# light-box-controller.net
KiCad netlist of a schematic drawn in EAGLE
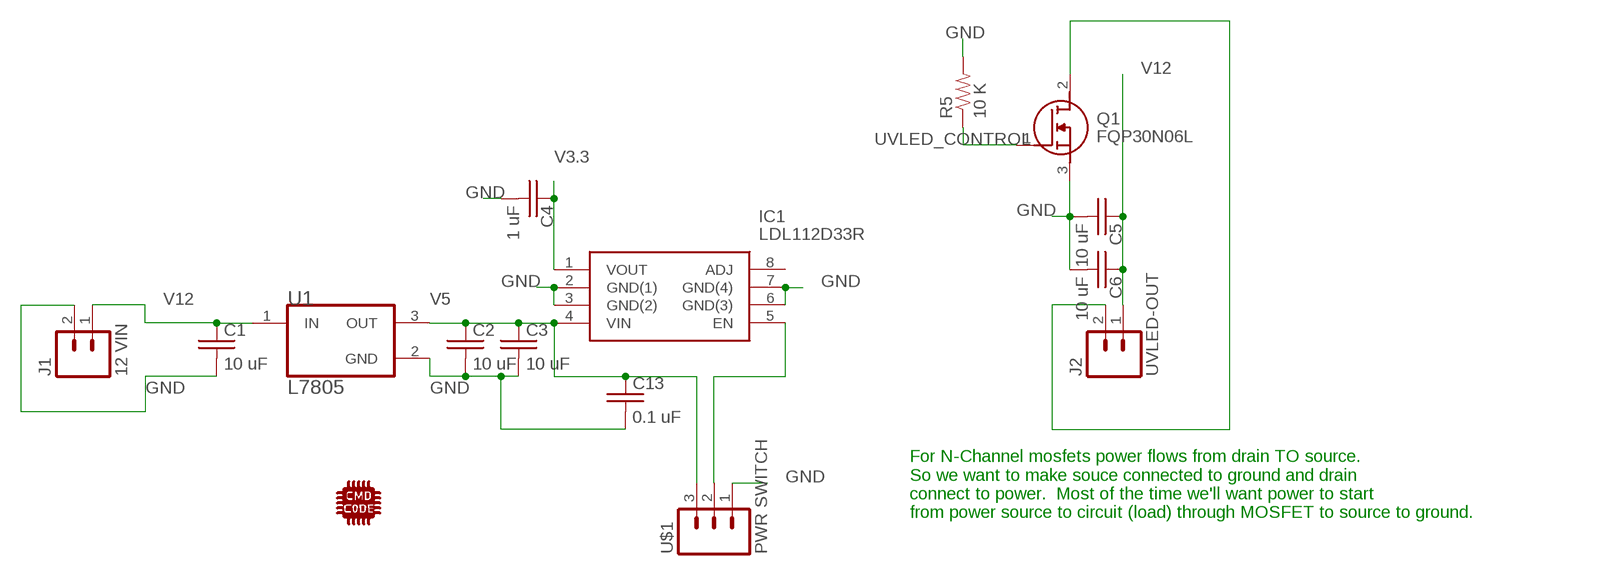
[diagram p0: schematic, sheet 1]
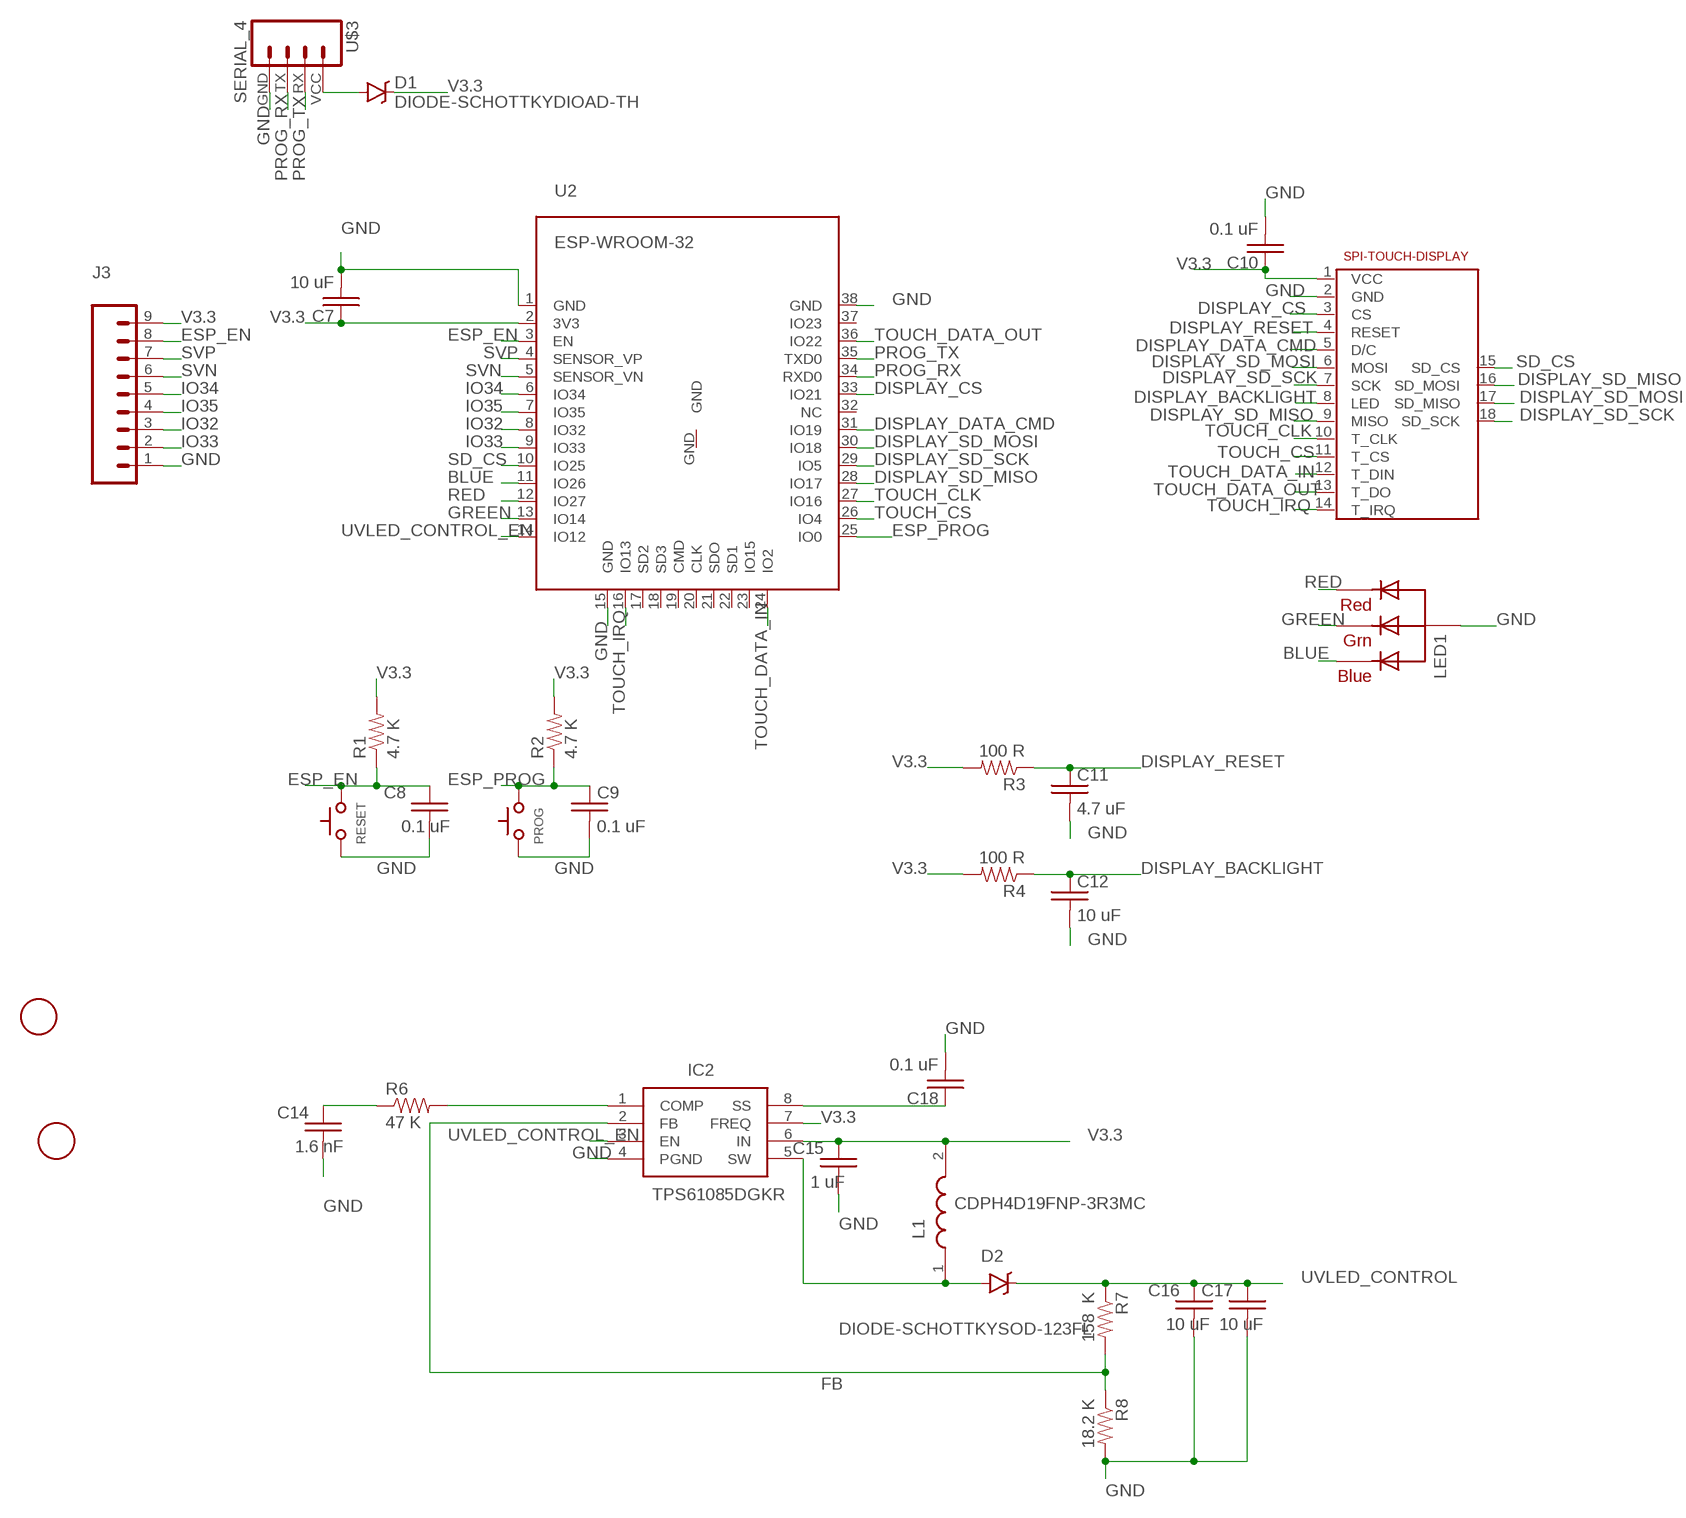
[diagram p1: schematic, sheet 2]

(export (version "E")
  (design (tool "Eeschema 10.0.6"))
  (components
    (comp (ref "C1")
      (value "10 uF")
      (footprint "eagle-import:C0805K")
      (libsource (lib "eagle-import") (part "C-USC0805K"))
    )
    (comp (ref "C2")
      (value "10 uF")
      (footprint "eagle-import:C0805K")
      (libsource (lib "eagle-import") (part "C-USC0805K"))
    )
    (comp (ref "C3")
      (value "10 uF")
      (footprint "eagle-import:C0805K")
      (libsource (lib "eagle-import") (part "C-USC0805K"))
    )
    (comp (ref "C4")
      (value "1 uF")
      (footprint "eagle-import:C0805K")
      (libsource (lib "eagle-import") (part "C-USC0805K"))
    )
    (comp (ref "C5")
      (value "10 uF")
      (footprint "eagle-import:C0805K")
      (libsource (lib "eagle-import") (part "C-USC0805K"))
    )
    (comp (ref "C6")
      (value "10 uF")
      (footprint "eagle-import:C0805K")
      (libsource (lib "eagle-import") (part "C-USC0805K"))
    )
    (comp (ref "C13")
      (value "0.1 uF")
      (footprint "eagle-import:C0805K")
      (libsource (lib "eagle-import") (part "C-USC0805K"))
    )
    (comp (ref "IC1")
      (value "LDL112D33R")
      (footprint "eagle-import:SOIC127P600X175-8N")
      (libsource (lib "eagle-import") (part "LDL112D33R"))
    )
    (comp (ref "J1")
      (value "12 VIN")
      (footprint "eagle-import:SCREWTERMINAL-5MM-2")
      (libsource (lib "eagle-import") (part "M025MM"))
    )
    (comp (ref "J2")
      (value "UVLED-OUT")
      (footprint "eagle-import:SCREWTERMINAL-5MM-2")
      (libsource (lib "eagle-import") (part "M025MM"))
    )
    (comp (ref "Q1")
      (value "FQP30N06L")
      (footprint "eagle-import:TO254P470X1016X2019-3P")
      (fields (field (name "MOUSER_PART_NUMBER") "512-FQP30N06L") (field (name "RS_PART_NUMBER") "8075863P"))
      (libsource (lib "eagle-import") (part "FQP30N06L"))
    )
    (comp (ref "R5")
      (value "10 K")
      (footprint "eagle-import:0805")
      (libsource (lib "eagle-import") (part "RESISTOR0805-RES"))
    )
    (comp (ref "U$1")
      (value "PWR SWITCH")
      (footprint "eagle-import:1X03_LONGPADS")
      (libsource (lib "eagle-import") (part "M03LONGPADS"))
    )
    (comp (ref "U$4")
      (value "CMD_C0DE_LOGOCMD_CODE_LOGO_SILK")
      (footprint "eagle-import:CMD_C0DE_LOGO_SILK")
      (libsource (lib "eagle-import") (part "CMD_C0DE_LOGOCMD_CODE_LOGO_SILK"))
    )
    (comp (ref "U1")
      (value "L7805")
      (footprint "eagle-import:TO-220-3")
      (fields (field (name "MF") "STMicroelectronics"))
      (libsource (lib "eagle-import") (part "L7805"))
    )
    (comp (ref "C7")
      (value "10 uF")
      (footprint "eagle-import:C0805K")
      (libsource (lib "eagle-import") (part "C-USC0805K"))
    )
    (comp (ref "C8")
      (value "0.1 uF")
      (footprint "eagle-import:C0805K")
      (libsource (lib "eagle-import") (part "C-USC0805K"))
    )
    (comp (ref "C9")
      (value "0.1 uF")
      (footprint "eagle-import:C0805K")
      (libsource (lib "eagle-import") (part "C-USC0805K"))
    )
    (comp (ref "C10")
      (value "0.1 uF")
      (footprint "eagle-import:C0805K")
      (libsource (lib "eagle-import") (part "C-USC0805K"))
    )
    (comp (ref "C11")
      (value "4.7 uF")
      (footprint "eagle-import:C0805K")
      (libsource (lib "eagle-import") (part "C-USC0805K"))
    )
    (comp (ref "C12")
      (value "10 uF")
      (footprint "eagle-import:C0805K")
      (libsource (lib "eagle-import") (part "C-USC0805K"))
    )
    (comp (ref "C14")
      (value "1.6 nF")
      (footprint "eagle-import:C0805K")
      (libsource (lib "eagle-import") (part "C-USC0805K"))
    )
    (comp (ref "C15")
      (value "1 uF")
      (footprint "eagle-import:C0805K")
      (libsource (lib "eagle-import") (part "C-USC0805K"))
    )
    (comp (ref "C16")
      (value "10 uF")
      (footprint "eagle-import:C0805K")
      (libsource (lib "eagle-import") (part "C-USC0805K"))
    )
    (comp (ref "C17")
      (value "10 uF")
      (footprint "eagle-import:C0805K")
      (libsource (lib "eagle-import") (part "C-USC0805K"))
    )
    (comp (ref "C18")
      (value "0.1 uF")
      (footprint "eagle-import:C0805K")
      (libsource (lib "eagle-import") (part "C-USC0805K"))
    )
    (comp (ref "D1")
      (value "DIODE-SCHOTTKYDIOAD-TH")
      (footprint "eagle-import:DIOAD1060W80L520D270")
      (libsource (lib "eagle-import") (part "DIODE-SCHOTTKYDIOAD-TH"))
    )
    (comp (ref "D2")
      (value "DIODE-SCHOTTKYSOD-123FL")
      (footprint "eagle-import:SOD-123FL")
      (libsource (lib "eagle-import") (part "DIODE-SCHOTTKYSOD-123FL"))
    )
    (comp (ref "IC2")
      (value "TPS61085DGKR")
      (footprint "eagle-import:SOP65P490X110-8N")
      (fields (field (name "MOUSER_PART_NUMBER") "595-TPS61085DGKR"))
      (libsource (lib "eagle-import") (part "TPS61085DGKR"))
    )
    (comp (ref "J3")
      (value "M09LONGPADS")
      (footprint "eagle-import:1X09_LONGPADS")
      (libsource (lib "eagle-import") (part "M09LONGPADS"))
    )
    (comp (ref "L1")
      (value "CDPH4D19FNP-3R3MC")
      (footprint "eagle-import:CDPH4D19FNP3R3MC")
      (fields (field (name "MOUSER_PART_NUMBER") "851-CDPH4D19FNP3R3MC"))
      (libsource (lib "eagle-import") (part "CDPH4D19FNP-3R3MC"))
    )
    (comp (ref "LED1")
      (value "RGBLED_CA-PIRANHA")
      (footprint "eagle-import:PIRANHA5MM")
      (libsource (lib "eagle-import") (part "RGBLED_CA-PIRANHA"))
    )
    (comp (ref "PROG")
      (value "SWITCH_TACTILETACTILE-2PIN-NARROW")
      (footprint "eagle-import:TACTILE-2PIN-NARROW")
      (libsource (lib "eagle-import") (part "SWITCH_TACTILETACTILE-2PIN-NARROW"))
    )
    (comp (ref "R1")
      (value "4.7 K")
      (footprint "eagle-import:0805")
      (libsource (lib "eagle-import") (part "RESISTOR0805-RES"))
    )
    (comp (ref "R2")
      (value "4.7 K")
      (footprint "eagle-import:0805")
      (libsource (lib "eagle-import") (part "RESISTOR0805-RES"))
    )
    (comp (ref "R3")
      (value "100 R")
      (footprint "eagle-import:0805")
      (libsource (lib "eagle-import") (part "RESISTOR0805-RES"))
    )
    (comp (ref "R4")
      (value "100 R")
      (footprint "eagle-import:0805")
      (libsource (lib "eagle-import") (part "RESISTOR0805-RES"))
    )
    (comp (ref "R6")
      (value "47 K")
      (footprint "eagle-import:0805")
      (libsource (lib "eagle-import") (part "RESISTOR0805-RES"))
    )
    (comp (ref "R7")
      (value "158 K")
      (footprint "eagle-import:0805")
      (libsource (lib "eagle-import") (part "RESISTOR0805-RES"))
    )
    (comp (ref "R8")
      (value "18.2 K")
      (footprint "eagle-import:0805")
      (libsource (lib "eagle-import") (part "RESISTOR0805-RES"))
    )
    (comp (ref "RESET")
      (value "SWITCH_TACTILETACTILE-2PIN-NARROW")
      (footprint "eagle-import:TACTILE-2PIN-NARROW")
      (libsource (lib "eagle-import") (part "SWITCH_TACTILETACTILE-2PIN-NARROW"))
    )
    (comp (ref "U$2")
      (value "2.4-SPI-TFT-TOUCH-SSD-MODULE")
      (footprint "eagle-import:2.4-SPI-TFT-TOUCH-SSD-MODULE")
      (libsource (lib "eagle-import") (part "2.4-SPI-TFT-TOUCH-SSD-MODULE"))
    )
    (comp (ref "U$3")
      (value "SERIAL_4")
      (footprint "eagle-import:SERIAL_HEADER_4")
      (libsource (lib "eagle-import") (part "SERIAL_4"))
    )
    (comp (ref "U$5")
      (value "FIDUCIAL")
      (footprint "eagle-import:FIDUCIAL_1MM")
      (libsource (lib "eagle-import") (part "FIDUCIAL"))
    )
    (comp (ref "U$6")
      (value "FIDUCIAL")
      (footprint "eagle-import:FIDUCIAL_1MM")
      (libsource (lib "eagle-import") (part "FIDUCIAL"))
    )
    (comp (ref "U2")
      (value "ESP-WROOM-32")
      (footprint "eagle-import:ESP-WROOM-32")
      (libsource (lib "eagle-import") (part "ESP-WROOM-32"))
    )
  )
  (nets
    (net (code "1") (name "BLUE") (class "Default")
      (node (ref "LED1") (pin "1") (pinfunction "BLUE_1") (pintype "bidirectional"))
      (node (ref "U2") (pin "11") (pinfunction "IO26_11") (pintype "bidirectional"))
    )
    (net (code "2") (name "DISPLAY_BACKLIGHT") (class "Default")
      (node (ref "C12") (pin "1") (pinfunction "1_1") (pintype "passive"))
      (node (ref "R4") (pin "1") (pinfunction "1_1") (pintype "passive"))
      (node (ref "U$2") (pin "8") (pinfunction "LED_8") (pintype "bidirectional"))
    )
    (net (code "3") (name "DISPLAY_CS") (class "Default")
      (node (ref "U$2") (pin "3") (pinfunction "CS_3") (pintype "bidirectional"))
      (node (ref "U2") (pin "33") (pinfunction "IO21_33") (pintype "bidirectional"))
    )
    (net (code "4") (name "DISPLAY_DATA_CMD") (class "Default")
      (node (ref "U$2") (pin "5") (pinfunction "D/C_5") (pintype "bidirectional"))
      (node (ref "U2") (pin "31") (pinfunction "IO19_31") (pintype "bidirectional"))
    )
    (net (code "5") (name "DISPLAY_RESET") (class "Default")
      (node (ref "C11") (pin "1") (pinfunction "1_1") (pintype "passive"))
      (node (ref "R3") (pin "1") (pinfunction "1_1") (pintype "passive"))
      (node (ref "U$2") (pin "4") (pinfunction "RESET_4") (pintype "bidirectional"))
    )
    (net (code "6") (name "DISPLAY_SD_MISO") (class "Default")
      (node (ref "U$2") (pin "16") (pinfunction "SD_MOSI_16") (pintype "bidirectional"))
      (node (ref "U$2") (pin "9") (pinfunction "MISO_9") (pintype "bidirectional"))
      (node (ref "U2") (pin "28") (pinfunction "IO17_28") (pintype "bidirectional"))
    )
    (net (code "7") (name "DISPLAY_SD_MOSI") (class "Default")
      (node (ref "U$2") (pin "17") (pinfunction "SD_MISO_17") (pintype "bidirectional"))
      (node (ref "U$2") (pin "6") (pinfunction "MOSI_6") (pintype "bidirectional"))
      (node (ref "U2") (pin "30") (pinfunction "IO18_30") (pintype "bidirectional"))
    )
    (net (code "8") (name "DISPLAY_SD_SCK") (class "Default")
      (node (ref "U$2") (pin "18") (pinfunction "SD_SCK_18") (pintype "bidirectional"))
      (node (ref "U$2") (pin "7") (pinfunction "SCK_7") (pintype "bidirectional"))
      (node (ref "U2") (pin "29") (pinfunction "IO5_29") (pintype "bidirectional"))
    )
    (net (code "9") (name "ESP_EN") (class "Default")
      (node (ref "C8") (pin "1") (pinfunction "1_1") (pintype "passive"))
      (node (ref "J3") (pin "8") (pinfunction "8_8") (pintype "passive"))
      (node (ref "R1") (pin "1") (pinfunction "1_1") (pintype "passive"))
      (node (ref "RESET") (pin "P$1") (pinfunction "A_P$1") (pintype "passive"))
      (node (ref "U2") (pin "3") (pinfunction "EN_3") (pintype "bidirectional"))
    )
    (net (code "10") (name "ESP_PROG") (class "Default")
      (node (ref "C9") (pin "1") (pinfunction "1_1") (pintype "passive"))
      (node (ref "PROG") (pin "P$1") (pinfunction "A_P$1") (pintype "passive"))
      (node (ref "R2") (pin "1") (pinfunction "1_1") (pintype "passive"))
      (node (ref "U2") (pin "25") (pinfunction "IO0_25") (pintype "bidirectional"))
    )
    (net (code "11") (name "FB") (class "Default")
      (node (ref "IC2") (pin "2") (pinfunction "FB_2") (pintype "bidirectional"))
      (node (ref "R7") (pin "2") (pinfunction "2_2") (pintype "passive"))
      (node (ref "R8") (pin "1") (pinfunction "1_1") (pintype "passive"))
    )
    (net (code "12") (name "GND") (class "Default")
      (node (ref "C1") (pin "2") (pinfunction "2_2") (pintype "passive"))
      (node (ref "C10") (pin "2") (pinfunction "2_2") (pintype "passive"))
      (node (ref "C11") (pin "2") (pinfunction "2_2") (pintype "passive"))
      (node (ref "C12") (pin "2") (pinfunction "2_2") (pintype "passive"))
      (node (ref "C13") (pin "2") (pinfunction "2_2") (pintype "passive"))
      (node (ref "C14") (pin "2") (pinfunction "2_2") (pintype "passive"))
      (node (ref "C15") (pin "2") (pinfunction "2_2") (pintype "passive"))
      (node (ref "C16") (pin "2") (pinfunction "2_2") (pintype "passive"))
      (node (ref "C17") (pin "2") (pinfunction "2_2") (pintype "passive"))
      (node (ref "C18") (pin "2") (pinfunction "2_2") (pintype "passive"))
      (node (ref "C2") (pin "2") (pinfunction "2_2") (pintype "passive"))
      (node (ref "C3") (pin "2") (pinfunction "2_2") (pintype "passive"))
      (node (ref "C4") (pin "2") (pinfunction "2_2") (pintype "passive"))
      (node (ref "C5") (pin "2") (pinfunction "2_2") (pintype "passive"))
      (node (ref "C6") (pin "2") (pinfunction "2_2") (pintype "passive"))
      (node (ref "C7") (pin "2") (pinfunction "2_2") (pintype "passive"))
      (node (ref "C8") (pin "2") (pinfunction "2_2") (pintype "passive"))
      (node (ref "C9") (pin "2") (pinfunction "2_2") (pintype "passive"))
      (node (ref "IC1") (pin "2") (pinfunction "GND(1)_2") (pintype "bidirectional"))
      (node (ref "IC1") (pin "3") (pinfunction "GND(2)_3") (pintype "bidirectional"))
      (node (ref "IC1") (pin "6") (pinfunction "GND(3)_6") (pintype "bidirectional"))
      (node (ref "IC1") (pin "7") (pinfunction "GND(4)_7") (pintype "bidirectional"))
      (node (ref "IC2") (pin "4") (pinfunction "PGND_4") (pintype "bidirectional"))
      (node (ref "J1") (pin "2") (pinfunction "2_2") (pintype "passive"))
      (node (ref "J3") (pin "1") (pinfunction "1_1") (pintype "passive"))
      (node (ref "LED1") (pin "4") (pinfunction "VCC_4") (pintype "bidirectional"))
      (node (ref "PROG") (pin "P$2") (pinfunction "C_P$2") (pintype "passive"))
      (node (ref "Q1") (pin "3") (pinfunction "S_3") (pintype "bidirectional"))
      (node (ref "R5") (pin "2") (pinfunction "2_2") (pintype "passive"))
      (node (ref "R8") (pin "2") (pinfunction "2_2") (pintype "passive"))
      (node (ref "RESET") (pin "P$2") (pinfunction "C_P$2") (pintype "passive"))
      (node (ref "U$1") (pin "1") (pinfunction "1_1") (pintype "passive"))
      (node (ref "U$2") (pin "2") (pinfunction "GND_2") (pintype "power_in"))
      (node (ref "U$3") (pin "GND") (pinfunction "GND_GND") (pintype "power_in"))
      (node (ref "U1") (pin "2") (pinfunction "GND_2") (pintype "power_in"))
      (node (ref "U2") (pin "1") (pinfunction "GND_1") (pintype "bidirectional"))
      (node (ref "U2") (pin "15") (pinfunction "GND_15") (pintype "bidirectional"))
      (node (ref "U2") (pin "38") (pinfunction "GND_38") (pintype "bidirectional"))
    )
    (net (code "13") (name "GREEN") (class "Default")
      (node (ref "LED1") (pin "3") (pinfunction "GREEN_3") (pintype "bidirectional"))
      (node (ref "U2") (pin "13") (pinfunction "IO14_13") (pintype "bidirectional"))
    )
    (net (code "14") (name "IO32") (class "Default")
      (node (ref "J3") (pin "3") (pinfunction "3_3") (pintype "passive"))
      (node (ref "U2") (pin "8") (pinfunction "IO32_8") (pintype "bidirectional"))
    )
    (net (code "15") (name "IO33") (class "Default")
      (node (ref "J3") (pin "2") (pinfunction "2_2") (pintype "passive"))
      (node (ref "U2") (pin "9") (pinfunction "IO33_9") (pintype "bidirectional"))
    )
    (net (code "16") (name "IO34") (class "Default")
      (node (ref "J3") (pin "5") (pinfunction "5_5") (pintype "passive"))
      (node (ref "U2") (pin "6") (pinfunction "IO34_6") (pintype "bidirectional"))
    )
    (net (code "17") (name "IO35") (class "Default")
      (node (ref "J3") (pin "4") (pinfunction "4_4") (pintype "passive"))
      (node (ref "U2") (pin "7") (pinfunction "IO35_7") (pintype "bidirectional"))
    )
    (net (code "18") (name "Net-(C14-Pad1)") (class "Default")
      (node (ref "C14") (pin "1") (pinfunction "1_1") (pintype "passive"))
      (node (ref "R6") (pin "1") (pinfunction "1_1") (pintype "passive"))
    )
    (net (code "19") (name "Net-(D1-PadA)") (class "Default")
      (node (ref "D1") (pin "A") (pinfunction "A_A") (pintype "passive"))
      (node (ref "U$3") (pin "VCC") (pinfunction "VCC_VCC") (pintype "power_in"))
    )
    (net (code "20") (name "Net-(IC1-EN)") (class "Default")
      (node (ref "IC1") (pin "5") (pinfunction "EN_5") (pintype "bidirectional"))
      (node (ref "U$1") (pin "2") (pinfunction "2_2") (pintype "passive"))
    )
    (net (code "21") (name "Net-(IC2-COMP)") (class "Default")
      (node (ref "IC2") (pin "1") (pinfunction "COMP_1") (pintype "bidirectional"))
      (node (ref "R6") (pin "2") (pinfunction "2_2") (pintype "passive"))
    )
    (net (code "22") (name "Net-(IC2-SS)") (class "Default")
      (node (ref "C18") (pin "1") (pinfunction "1_1") (pintype "passive"))
      (node (ref "IC2") (pin "8") (pinfunction "SS_8") (pintype "bidirectional"))
    )
    (net (code "23") (name "Net-(IC2-SW)") (class "Default")
      (node (ref "D2") (pin "A") (pinfunction "A_A") (pintype "passive"))
      (node (ref "IC2") (pin "5") (pinfunction "SW_5") (pintype "bidirectional"))
      (node (ref "L1") (pin "1") (pinfunction "1_1") (pintype "bidirectional"))
    )
    (net (code "24") (name "Net-(Q1-D)") (class "Default")
      (node (ref "J2") (pin "2") (pinfunction "2_2") (pintype "passive"))
      (node (ref "Q1") (pin "2") (pinfunction "D_2") (pintype "bidirectional"))
    )
    (net (code "25") (name "PROG_RX") (class "Default")
      (node (ref "U$3") (pin "TX") (pinfunction "TX_TX") (pintype "input"))
      (node (ref "U2") (pin "34") (pinfunction "RXD0_34") (pintype "bidirectional"))
    )
    (net (code "26") (name "PROG_TX") (class "Default")
      (node (ref "U$3") (pin "RX") (pinfunction "RX_RX") (pintype "bidirectional"))
      (node (ref "U2") (pin "35") (pinfunction "TXD0_35") (pintype "bidirectional"))
    )
    (net (code "27") (name "RED") (class "Default")
      (node (ref "LED1") (pin "2") (pinfunction "RED_2") (pintype "bidirectional"))
      (node (ref "U2") (pin "12") (pinfunction "IO27_12") (pintype "bidirectional"))
    )
    (net (code "28") (name "SD_CS") (class "Default")
      (node (ref "U$2") (pin "15") (pinfunction "SD_CS_15") (pintype "bidirectional"))
      (node (ref "U2") (pin "10") (pinfunction "IO25_10") (pintype "bidirectional"))
    )
    (net (code "29") (name "SVN") (class "Default")
      (node (ref "J3") (pin "6") (pinfunction "6_6") (pintype "passive"))
      (node (ref "U2") (pin "5") (pinfunction "SENSOR_VN_5") (pintype "bidirectional"))
    )
    (net (code "30") (name "SVP") (class "Default")
      (node (ref "J3") (pin "7") (pinfunction "7_7") (pintype "passive"))
      (node (ref "U2") (pin "4") (pinfunction "SENSOR_VP_4") (pintype "bidirectional"))
    )
    (net (code "31") (name "TOUCH_CLK") (class "Default")
      (node (ref "U$2") (pin "10") (pinfunction "T_CLK_10") (pintype "bidirectional"))
      (node (ref "U2") (pin "27") (pinfunction "IO16_27") (pintype "bidirectional"))
    )
    (net (code "32") (name "TOUCH_CS") (class "Default")
      (node (ref "U$2") (pin "11") (pinfunction "T_CS_11") (pintype "bidirectional"))
      (node (ref "U2") (pin "26") (pinfunction "IO4_26") (pintype "bidirectional"))
    )
    (net (code "33") (name "TOUCH_DATA_IN") (class "Default")
      (node (ref "U$2") (pin "12") (pinfunction "T_DIN_12") (pintype "bidirectional"))
      (node (ref "U2") (pin "24") (pinfunction "IO2_24") (pintype "bidirectional"))
    )
    (net (code "34") (name "TOUCH_DATA_OUT") (class "Default")
      (node (ref "U$2") (pin "13") (pinfunction "T_DO_13") (pintype "bidirectional"))
      (node (ref "U2") (pin "36") (pinfunction "IO22_36") (pintype "bidirectional"))
    )
    (net (code "35") (name "TOUCH_IRQ") (class "Default")
      (node (ref "U$2") (pin "14") (pinfunction "T_IRQ_14") (pintype "bidirectional"))
      (node (ref "U2") (pin "16") (pinfunction "IO13_16") (pintype "bidirectional"))
    )
    (net (code "36") (name "UVLED_CONTROL") (class "Default")
      (node (ref "C16") (pin "1") (pinfunction "1_1") (pintype "passive"))
      (node (ref "C17") (pin "1") (pinfunction "1_1") (pintype "passive"))
      (node (ref "D2") (pin "C") (pinfunction "C_C") (pintype "passive"))
      (node (ref "Q1") (pin "1") (pinfunction "G_1") (pintype "bidirectional"))
      (node (ref "R5") (pin "1") (pinfunction "1_1") (pintype "passive"))
      (node (ref "R7") (pin "1") (pinfunction "1_1") (pintype "passive"))
    )
    (net (code "37") (name "UVLED_CONTROL_EN") (class "Default")
      (node (ref "IC2") (pin "3") (pinfunction "EN_3") (pintype "bidirectional"))
      (node (ref "U2") (pin "14") (pinfunction "IO12_14") (pintype "bidirectional"))
    )
    (net (code "38") (name "V3.3") (class "Default")
      (node (ref "C10") (pin "1") (pinfunction "1_1") (pintype "passive"))
      (node (ref "C15") (pin "1") (pinfunction "1_1") (pintype "passive"))
      (node (ref "C4") (pin "1") (pinfunction "1_1") (pintype "passive"))
      (node (ref "C7") (pin "1") (pinfunction "1_1") (pintype "passive"))
      (node (ref "D1") (pin "C") (pinfunction "C_C") (pintype "passive"))
      (node (ref "IC1") (pin "1") (pinfunction "VOUT_1") (pintype "bidirectional"))
      (node (ref "IC2") (pin "6") (pinfunction "IN_6") (pintype "bidirectional"))
      (node (ref "IC2") (pin "7") (pinfunction "FREQ_7") (pintype "bidirectional"))
      (node (ref "J3") (pin "9") (pinfunction "9_9") (pintype "passive"))
      (node (ref "L1") (pin "2") (pinfunction "2_2") (pintype "bidirectional"))
      (node (ref "R1") (pin "2") (pinfunction "2_2") (pintype "passive"))
      (node (ref "R2") (pin "2") (pinfunction "2_2") (pintype "passive"))
      (node (ref "R3") (pin "2") (pinfunction "2_2") (pintype "passive"))
      (node (ref "R4") (pin "2") (pinfunction "2_2") (pintype "passive"))
      (node (ref "U$2") (pin "1") (pinfunction "VCC_1") (pintype "power_in"))
      (node (ref "U2") (pin "2") (pinfunction "3V3_2") (pintype "bidirectional"))
    )
    (net (code "39") (name "V5") (class "Default")
      (node (ref "C13") (pin "1") (pinfunction "1_1") (pintype "passive"))
      (node (ref "C2") (pin "1") (pinfunction "1_1") (pintype "passive"))
      (node (ref "C3") (pin "1") (pinfunction "1_1") (pintype "passive"))
      (node (ref "IC1") (pin "4") (pinfunction "VIN_4") (pintype "bidirectional"))
      (node (ref "U$1") (pin "3") (pinfunction "3_3") (pintype "passive"))
      (node (ref "U1") (pin "3") (pinfunction "OUT_3") (pintype "output"))
    )
    (net (code "40") (name "V12") (class "Default")
      (node (ref "C1") (pin "1") (pinfunction "1_1") (pintype "passive"))
      (node (ref "C5") (pin "1") (pinfunction "1_1") (pintype "passive"))
      (node (ref "C6") (pin "1") (pinfunction "1_1") (pintype "passive"))
      (node (ref "J1") (pin "1") (pinfunction "1_1") (pintype "passive"))
      (node (ref "J2") (pin "1") (pinfunction "1_1") (pintype "passive"))
      (node (ref "U1") (pin "1") (pinfunction "IN_1") (pintype "input"))
    )
    (net (code "41") (name "unconnected-(IC1-ADJ-Pad8)") (class "Default")
      (node (ref "IC1") (pin "8") (pinfunction "ADJ_8") (pintype "bidirectional"))
    )
    (net (code "42") (name "unconnected-(U2-CLK-Pad20)") (class "Default")
      (node (ref "U2") (pin "20") (pinfunction "CLK_20") (pintype "bidirectional"))
    )
    (net (code "43") (name "unconnected-(U2-CMD-Pad19)") (class "Default")
      (node (ref "U2") (pin "19") (pinfunction "CMD_19") (pintype "bidirectional"))
    )
    (net (code "44") (name "unconnected-(U2-IO15-Pad23)") (class "Default")
      (node (ref "U2") (pin "23") (pinfunction "IO15_23") (pintype "bidirectional"))
    )
    (net (code "45") (name "unconnected-(U2-IO23-Pad37)") (class "Default")
      (node (ref "U2") (pin "37") (pinfunction "IO23_37") (pintype "bidirectional"))
    )
    (net (code "46") (name "unconnected-(U2-NC-Pad32)") (class "Default")
      (node (ref "U2") (pin "32") (pinfunction "NC_32") (pintype "bidirectional"))
    )
    (net (code "47") (name "unconnected-(U2-PadGND)") (class "Default")
      (node (ref "U2") (pin "GND") (pinfunction "GND_GND") (pintype "bidirectional"))
    )
    (net (code "48") (name "unconnected-(U2-SD1-Pad22)") (class "Default")
      (node (ref "U2") (pin "22") (pinfunction "SD1_22") (pintype "bidirectional"))
    )
    (net (code "49") (name "unconnected-(U2-SD2-Pad17)") (class "Default")
      (node (ref "U2") (pin "17") (pinfunction "SD2_17") (pintype "bidirectional"))
    )
    (net (code "50") (name "unconnected-(U2-SD3-Pad18)") (class "Default")
      (node (ref "U2") (pin "18") (pinfunction "SD3_18") (pintype "bidirectional"))
    )
    (net (code "51") (name "unconnected-(U2-SDO-Pad21)") (class "Default")
      (node (ref "U2") (pin "21") (pinfunction "SDO_21") (pintype "bidirectional"))
    )
  )
)
